# Modular-LED-Lamp-Power-Control.net
KiCad netlist of a schematic drawn in EAGLE
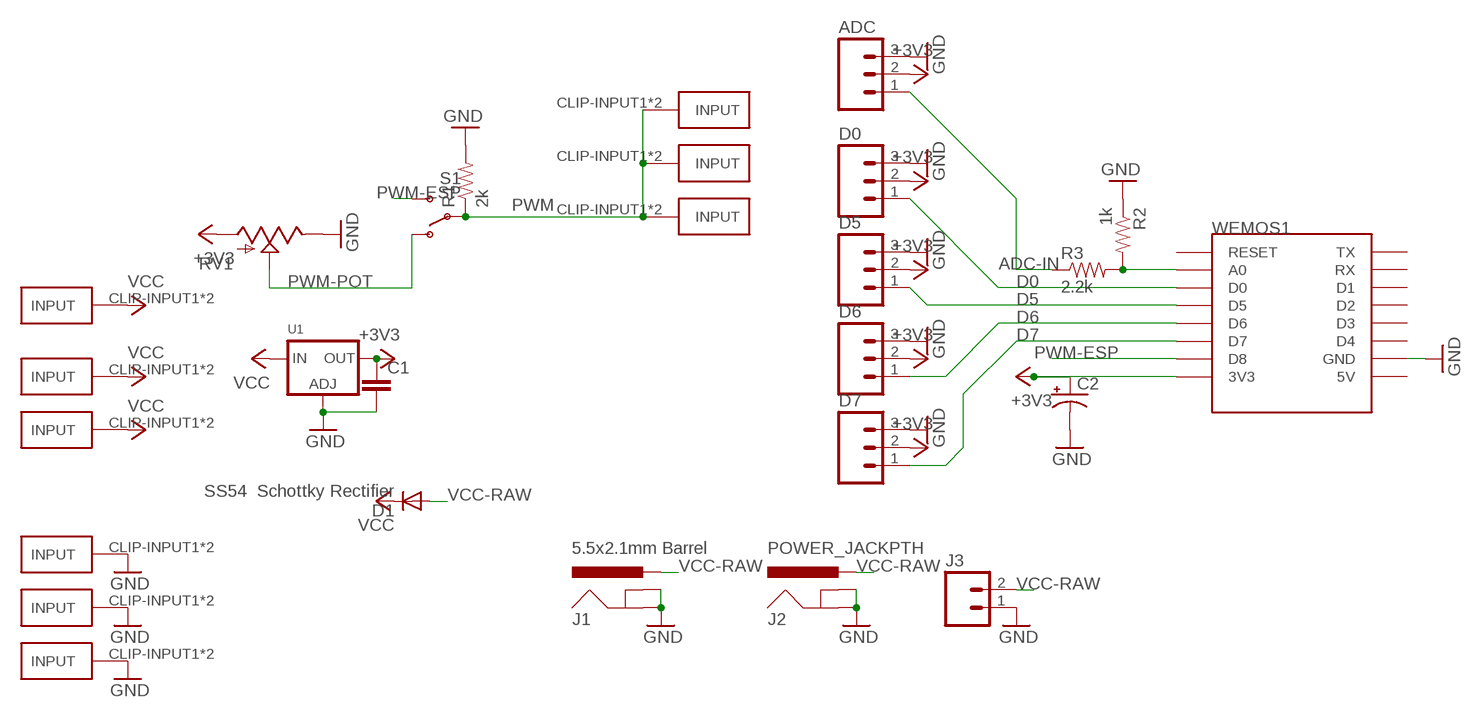
[diagram p0: schematic, sheet 1]

(export (version "E")
  (design (tool "Eeschema 10.0.6"))
  (components
    (comp (ref "ADC")
      (value "M03PTH")
      (footprint "eagle-import:1X03")
      (libsource (lib "eagle-import") (part "M03PTH"))
    )
    (comp (ref "C1")
      (value "CAP1206")
      (footprint "eagle-import:1206")
      (libsource (lib "eagle-import") (part "CAP1206"))
    )
    (comp (ref "C2")
      (value "CAP_POLE")
      (footprint "eagle-import:PANASONIC_E")
      (libsource (lib "eagle-import") (part "CAP_POLE"))
    )
    (comp (ref "D0")
      (value "M03PTH")
      (footprint "eagle-import:1X03")
      (libsource (lib "eagle-import") (part "M03PTH"))
    )
    (comp (ref "D1")
      (value "SS54 Schottky Rectifier")
      (footprint "eagle-import:DO214AB")
      (fields (field (name "MF") "Fairchild") (field (name "MPN") "S3A"))
      (libsource (lib "eagle-import") (part "S3A"))
    )
    (comp (ref "D5")
      (value "M03PTH")
      (footprint "eagle-import:1X03")
      (libsource (lib "eagle-import") (part "M03PTH"))
    )
    (comp (ref "D6")
      (value "M03PTH")
      (footprint "eagle-import:1X03")
      (libsource (lib "eagle-import") (part "M03PTH"))
    )
    (comp (ref "D7")
      (value "M03PTH")
      (footprint "eagle-import:1X03")
      (libsource (lib "eagle-import") (part "M03PTH"))
    )
    (comp (ref "GND-CLIP")
      (value "GND")
      (footprint "eagle-import:FUSE-HOLDER-5X20MM")
      (libsource (lib "eagle-import") (part "FUSE-HOLDER-5X20MM"))
    )
    (comp (ref "GND-CLIP1")
      (value "GND")
      (footprint "eagle-import:FUSE-HOLDER-5X20MM")
      (libsource (lib "eagle-import") (part "FUSE-HOLDER-5X20MM"))
    )
    (comp (ref "GND-CLIP2")
      (value "GND")
      (footprint "eagle-import:FUSE-HOLDER-5X20MM")
      (libsource (lib "eagle-import") (part "FUSE-HOLDER-5X20MM"))
    )
    (comp (ref "J1")
      (value "5.5x2.1mm Barrel")
      (footprint "eagle-import:POWER_JACK_SMD")
      (libsource (lib "eagle-import") (part "POWER_JACKSMD"))
    )
    (comp (ref "J2")
      (value "POWER_JACKPTH")
      (footprint "eagle-import:POWER_JACK_PTH")
      (libsource (lib "eagle-import") (part "POWER_JACKPTH"))
    )
    (comp (ref "J3")
      (value "M025MM")
      (footprint "eagle-import:SCREWTERMINAL-5MM-2")
      (libsource (lib "eagle-import") (part "M025MM"))
    )
    (comp (ref "PWM-CLIP")
      (value "FUSE-HOLDER-5X20MM")
      (footprint "eagle-import:FUSE-HOLDER-5X20MM")
      (libsource (lib "eagle-import") (part "FUSE-HOLDER-5X20MM"))
    )
    (comp (ref "PWM-CLIP1")
      (value "FUSE-HOLDER-5X20MM")
      (footprint "eagle-import:FUSE-HOLDER-5X20MM")
      (libsource (lib "eagle-import") (part "FUSE-HOLDER-5X20MM"))
    )
    (comp (ref "PWM-CLIP2")
      (value "FUSE-HOLDER-5X20MM")
      (footprint "eagle-import:FUSE-HOLDER-5X20MM")
      (libsource (lib "eagle-import") (part "FUSE-HOLDER-5X20MM"))
    )
    (comp (ref "R1")
      (value "2k")
      (footprint "eagle-import:1206")
      (libsource (lib "eagle-import") (part "RESISTOR1206"))
    )
    (comp (ref "R2")
      (value "1k")
      (footprint "eagle-import:1206")
      (libsource (lib "eagle-import") (part "RESISTOR1206"))
    )
    (comp (ref "R3")
      (value "2.2k")
      (footprint "eagle-import:1206")
      (libsource (lib "eagle-import") (part "RESISTOR1206"))
    )
    (comp (ref "RV1")
      (value "POT-RV16AF-20")
      (footprint "eagle-import:POT_ALPHA_RV16AF-20")
      (libsource (lib "eagle-import") (part "POT-RV16AF-20"))
    )
    (comp (ref "S1")
      (value "SWITCH-SPDTPTH")
      (footprint "eagle-import:SWITCH-SPDT")
      (libsource (lib "eagle-import") (part "SWITCH-SPDTPTH"))
    )
    (comp (ref "U1")
      (value "LM1117SOT223-WAVE")
      (footprint "eagle-import:SOT223-W")
      (libsource (lib "eagle-import") (part "LM1117SOT223-WAVE"))
    )
    (comp (ref "VCC-CLIP")
      (value "FUSE-HOLDER-5X20MM")
      (footprint "eagle-import:FUSE-HOLDER-5X20MM")
      (libsource (lib "eagle-import") (part "FUSE-HOLDER-5X20MM"))
    )
    (comp (ref "VCC-CLIP1")
      (value "FUSE-HOLDER-5X20MM")
      (footprint "eagle-import:FUSE-HOLDER-5X20MM")
      (libsource (lib "eagle-import") (part "FUSE-HOLDER-5X20MM"))
    )
    (comp (ref "VCC-CLIP2")
      (value "FUSE-HOLDER-5X20MM")
      (footprint "eagle-import:FUSE-HOLDER-5X20MM")
      (libsource (lib "eagle-import") (part "FUSE-HOLDER-5X20MM"))
    )
    (comp (ref "WEMOS1")
      (value "WEMOS-D1-MINI")
      (footprint "eagle-import:WEMOS-D1-MINI")
      (libsource (lib "eagle-import") (part "WEMOS-D1-MINI"))
    )
  )
  (nets
    (net (code "1") (name "+3V3") (class "Default")
      (node (ref "ADC") (pin "2") (pinfunction "2_2") (pintype "passive"))
      (node (ref "C1") (pin "1") (pinfunction "1_1") (pintype "passive"))
      (node (ref "C2") (pin "+") (pinfunction "+_+") (pintype "passive"))
      (node (ref "D0") (pin "2") (pinfunction "2_2") (pintype "passive"))
      (node (ref "D5") (pin "2") (pinfunction "2_2") (pintype "passive"))
      (node (ref "D6") (pin "2") (pinfunction "2_2") (pintype "passive"))
      (node (ref "D7") (pin "2") (pinfunction "2_2") (pintype "passive"))
      (node (ref "RV1") (pin "1") (pinfunction "A_1") (pintype "passive"))
      (node (ref "U1") (pin "2") (pinfunction "OUT_2") (pintype "passive"))
      (node (ref "WEMOS1") (pin "3V3") (pinfunction "3V3_3V3") (pintype "bidirectional"))
    )
    (net (code "2") (name "/ADC-IN") (class "Default")
      (node (ref "ADC") (pin "1") (pinfunction "1_1") (pintype "passive"))
      (node (ref "R3") (pin "1") (pinfunction "1_1") (pintype "passive"))
    )
    (net (code "3") (name "/D0") (class "Default")
      (node (ref "D0") (pin "1") (pinfunction "1_1") (pintype "passive"))
      (node (ref "WEMOS1") (pin "D0") (pinfunction "D0_D0") (pintype "bidirectional"))
    )
    (net (code "4") (name "/D5") (class "Default")
      (node (ref "D5") (pin "1") (pinfunction "1_1") (pintype "passive"))
      (node (ref "WEMOS1") (pin "D5") (pinfunction "D5_D5") (pintype "bidirectional"))
    )
    (net (code "5") (name "/D6") (class "Default")
      (node (ref "D6") (pin "1") (pinfunction "1_1") (pintype "passive"))
      (node (ref "WEMOS1") (pin "D6") (pinfunction "D6_D6") (pintype "bidirectional"))
    )
    (net (code "6") (name "/D7") (class "Default")
      (node (ref "D7") (pin "1") (pinfunction "1_1") (pintype "passive"))
      (node (ref "WEMOS1") (pin "D7") (pinfunction "D7_D7") (pintype "bidirectional"))
    )
    (net (code "7") (name "/PWM") (class "Default")
      (node (ref "PWM-CLIP") (pin "CLIP-INPUT1") (pinfunction "INPUT_CLIP-INPUT1") (pintype "bidirectional"))
      (node (ref "PWM-CLIP") (pin "CLIP-INPUT2") (pinfunction "INPUT_CLIP-INPUT2") (pintype "bidirectional"))
      (node (ref "PWM-CLIP1") (pin "CLIP-INPUT1") (pinfunction "INPUT_CLIP-INPUT1") (pintype "bidirectional"))
      (node (ref "PWM-CLIP1") (pin "CLIP-INPUT2") (pinfunction "INPUT_CLIP-INPUT2") (pintype "bidirectional"))
      (node (ref "PWM-CLIP2") (pin "CLIP-INPUT1") (pinfunction "INPUT_CLIP-INPUT1") (pintype "bidirectional"))
      (node (ref "PWM-CLIP2") (pin "CLIP-INPUT2") (pinfunction "INPUT_CLIP-INPUT2") (pintype "bidirectional"))
      (node (ref "R1") (pin "1") (pinfunction "1_1") (pintype "passive"))
      (node (ref "S1") (pin "2") (pinfunction "P_2") (pintype "passive"))
    )
    (net (code "8") (name "/PWM-ESP") (class "Default")
      (node (ref "S1") (pin "3") (pinfunction "S_3") (pintype "passive"))
      (node (ref "WEMOS1") (pin "D8") (pinfunction "D8_D8") (pintype "bidirectional"))
    )
    (net (code "9") (name "/PWM-POT") (class "Default")
      (node (ref "RV1") (pin "2") (pinfunction "S_2") (pintype "passive"))
      (node (ref "S1") (pin "1") (pinfunction "O_1") (pintype "passive"))
    )
    (net (code "10") (name "/VCC-RAW") (class "Default")
      (node (ref "D1") (pin "A") (pinfunction "A_A") (pintype "passive"))
      (node (ref "J1") (pin "VIN0") (pinfunction "PWR_VIN0") (pintype "bidirectional"))
      (node (ref "J2") (pin "PWR") (pinfunction "PWR_PWR") (pintype "bidirectional"))
      (node (ref "J3") (pin "2") (pinfunction "2_2") (pintype "passive"))
    )
    (net (code "11") (name "GND") (class "Default")
      (node (ref "ADC") (pin "3") (pinfunction "3_3") (pintype "passive"))
      (node (ref "C1") (pin "2") (pinfunction "2_2") (pintype "passive"))
      (node (ref "C2") (pin "-") (pinfunction "-_-") (pintype "passive"))
      (node (ref "D0") (pin "3") (pinfunction "3_3") (pintype "passive"))
      (node (ref "D5") (pin "3") (pinfunction "3_3") (pintype "passive"))
      (node (ref "D6") (pin "3") (pinfunction "3_3") (pintype "passive"))
      (node (ref "D7") (pin "3") (pinfunction "3_3") (pintype "passive"))
      (node (ref "GND-CLIP") (pin "CLIP-INPUT1") (pinfunction "INPUT_CLIP-INPUT1") (pintype "bidirectional"))
      (node (ref "GND-CLIP") (pin "CLIP-INPUT2") (pinfunction "INPUT_CLIP-INPUT2") (pintype "bidirectional"))
      (node (ref "GND-CLIP1") (pin "CLIP-INPUT1") (pinfunction "INPUT_CLIP-INPUT1") (pintype "bidirectional"))
      (node (ref "GND-CLIP1") (pin "CLIP-INPUT2") (pinfunction "INPUT_CLIP-INPUT2") (pintype "bidirectional"))
      (node (ref "GND-CLIP2") (pin "CLIP-INPUT1") (pinfunction "INPUT_CLIP-INPUT1") (pintype "bidirectional"))
      (node (ref "GND-CLIP2") (pin "CLIP-INPUT2") (pinfunction "INPUT_CLIP-INPUT2") (pintype "bidirectional"))
      (node (ref "J1") (pin "GND") (pinfunction "GNDBREAK_GND") (pintype "bidirectional"))
      (node (ref "J1") (pin "P$4") (pinfunction "GND_P$4") (pintype "bidirectional"))
      (node (ref "J2") (pin "GND") (pinfunction "GND_GND") (pintype "bidirectional"))
      (node (ref "J2") (pin "GNDBREAK") (pinfunction "GNDBREAK_GNDBREAK") (pintype "bidirectional"))
      (node (ref "J3") (pin "1") (pinfunction "1_1") (pintype "passive"))
      (node (ref "R1") (pin "2") (pinfunction "2_2") (pintype "passive"))
      (node (ref "R2") (pin "1") (pinfunction "1_1") (pintype "passive"))
      (node (ref "RV1") (pin "3") (pinfunction "E_3") (pintype "passive"))
      (node (ref "U1") (pin "1") (pinfunction "ADJ_1") (pintype "input"))
      (node (ref "WEMOS1") (pin "GND") (pinfunction "GND_GND") (pintype "bidirectional"))
    )
    (net (code "12") (name "Net-(R2-Pad2)") (class "Default")
      (node (ref "R2") (pin "2") (pinfunction "2_2") (pintype "passive"))
      (node (ref "R3") (pin "2") (pinfunction "2_2") (pintype "passive"))
      (node (ref "WEMOS1") (pin "A0") (pinfunction "A0_A0") (pintype "bidirectional"))
    )
    (net (code "13") (name "VCC") (class "Default")
      (node (ref "D1") (pin "C") (pinfunction "C_C") (pintype "passive"))
      (node (ref "U1") (pin "3") (pinfunction "IN_3") (pintype "input"))
      (node (ref "VCC-CLIP") (pin "CLIP-INPUT1") (pinfunction "INPUT_CLIP-INPUT1") (pintype "bidirectional"))
      (node (ref "VCC-CLIP") (pin "CLIP-INPUT2") (pinfunction "INPUT_CLIP-INPUT2") (pintype "bidirectional"))
      (node (ref "VCC-CLIP1") (pin "CLIP-INPUT1") (pinfunction "INPUT_CLIP-INPUT1") (pintype "bidirectional"))
      (node (ref "VCC-CLIP1") (pin "CLIP-INPUT2") (pinfunction "INPUT_CLIP-INPUT2") (pintype "bidirectional"))
      (node (ref "VCC-CLIP2") (pin "CLIP-INPUT1") (pinfunction "INPUT_CLIP-INPUT1") (pintype "bidirectional"))
      (node (ref "VCC-CLIP2") (pin "CLIP-INPUT2") (pinfunction "INPUT_CLIP-INPUT2") (pintype "bidirectional"))
    )
    (net (code "14") (name "unconnected-(WEMOS1-Pad5V)") (class "Default")
      (node (ref "WEMOS1") (pin "5V") (pinfunction "5V_5V") (pintype "bidirectional"))
    )
    (net (code "15") (name "unconnected-(WEMOS1-PadD1)") (class "Default")
      (node (ref "WEMOS1") (pin "D1") (pinfunction "D1_D1") (pintype "bidirectional"))
    )
    (net (code "16") (name "unconnected-(WEMOS1-PadD2)") (class "Default")
      (node (ref "WEMOS1") (pin "D2") (pinfunction "D2_D2") (pintype "bidirectional"))
    )
    (net (code "17") (name "unconnected-(WEMOS1-PadD3)") (class "Default")
      (node (ref "WEMOS1") (pin "D3") (pinfunction "D3_D3") (pintype "bidirectional"))
    )
    (net (code "18") (name "unconnected-(WEMOS1-PadD4)") (class "Default")
      (node (ref "WEMOS1") (pin "D4") (pinfunction "D4_D4") (pintype "bidirectional"))
    )
    (net (code "19") (name "unconnected-(WEMOS1-PadRESET)") (class "Default")
      (node (ref "WEMOS1") (pin "RESET") (pinfunction "RESET_RESET") (pintype "bidirectional"))
    )
    (net (code "20") (name "unconnected-(WEMOS1-PadRX)") (class "Default")
      (node (ref "WEMOS1") (pin "RX") (pinfunction "RX_RX") (pintype "bidirectional"))
    )
    (net (code "21") (name "unconnected-(WEMOS1-PadTX)") (class "Default")
      (node (ref "WEMOS1") (pin "TX") (pinfunction "TX_TX") (pintype "bidirectional"))
    )
  )
)
